# 2_IOConvert.net
KiCad netlist of a schematic drawn in Altium Designer
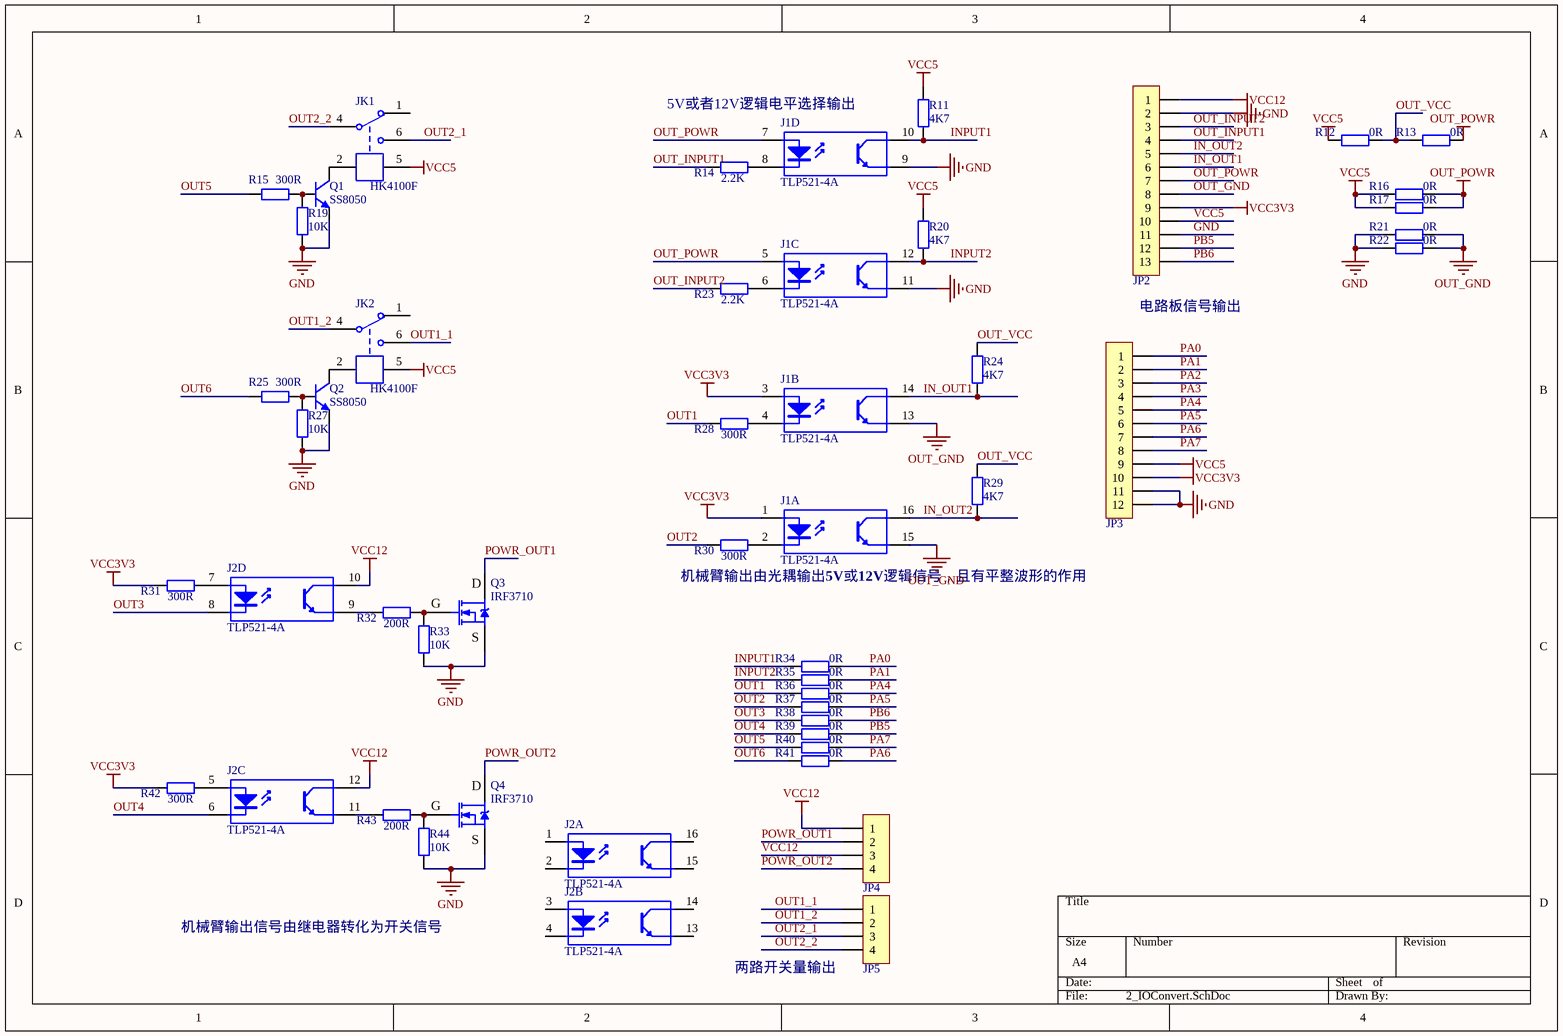
[diagram p0: 2_IOConvert.SchDoc]

(export (version "E")
  (design (tool "Eeschema 10.0.6"))
  (components
    (comp (ref "J1")
      (value "TLP521-4A")
      (footprint "SOP16_M")
      (description "4路开关光耦")
      (fields (field (name "版权归属") "源创客"))
      (libsource (lib "11.1 - 传感元件") (part "TLP521-4A"))
    )
    (comp (ref "J2")
      (value "TLP521-4A")
      (footprint "SOP16_M")
      (description "4路开关光耦")
      (fields (field (name "版权归属") "源创客"))
      (libsource (lib "11.1 - 传感元件") (part "TLP521-4A"))
    )
    (comp (ref "JK1")
      (value "HK4100F")
      (footprint "HK4100F")
      (description "一组转换")
      (fields (field (name "版权归属") "源创客"))
      (libsource (lib "7.1   - 继电器") (part "HK4100F"))
    )
    (comp (ref "JK2")
      (value "HK4100F")
      (footprint "HK4100F")
      (description "一组转换")
      (fields (field (name "版权归属") "源创客"))
      (libsource (lib "7.1   - 继电器") (part "HK4100F"))
    )
    (comp (ref "JP2")
      (value "HDR-1X13")
      (footprint "KF128-3.81-13P")
      (description "13P接插件")
      (fields (field (name "版权归属") "源创客"))
      (libsource (lib "4.7   - 接插件-脚距3.81") (part "Header 13"))
    )
    (comp (ref "JP3")
      (value "HDR-1X12")
      (footprint "KF128-3.81-12P")
      (description "12P接插件")
      (fields (field (name "版权归属") "源创客"))
      (libsource (lib "4.7   - 接插件-脚距3.81") (part "Header 12"))
    )
    (comp (ref "JP4")
      (value "HDR-1X4")
      (footprint "KF128-3.81-4P")
      (description "4P接插件")
      (fields (field (name "版权归属") "源创客"))
      (libsource (lib "4.7   - 接插件-脚距3.81") (part "Header 4"))
    )
    (comp (ref "JP5")
      (value "HDR-1X4")
      (footprint "KF128-3.81-4P")
      (description "4P接插件")
      (fields (field (name "版权归属") "源创客"))
      (libsource (lib "4.7   - 接插件-脚距3.81") (part "Header 4"))
    )
    (comp (ref "Q1")
      (value "SS8050")
      (footprint "SOT23-3L")
      (description "高频放大-NPN型")
      (fields (field (name "版权归属") "源创客"))
      (libsource (lib "6.2   - 三极管") (part "8050-SMD"))
    )
    (comp (ref "Q2")
      (value "SS8050")
      (footprint "SOT23-3L")
      (description "高频放大-NPN型")
      (fields (field (name "版权归属") "源创客"))
      (libsource (lib "6.2   - 三极管") (part "8050-SMD"))
    )
    (comp (ref "Q3")
      (value "IRF3710")
      (footprint "TO252")
      (description "N沟场效应管")
      (fields (field (name "版权归属") "源创客"))
      (libsource (lib "6.1   - 场效应管-可控硅") (part "IRF3710"))
    )
    (comp (ref "Q4")
      (value "IRF3710")
      (footprint "TO252")
      (description "N沟场效应管")
      (fields (field (name "版权归属") "源创客"))
      (libsource (lib "6.1   - 场效应管-可控硅") (part "IRF3710"))
    )
    (comp (ref "R11")
      (value "4K7")
      (footprint "LC-0603_R")
      (description "贴片电阻")
      (libsource (lib "") (part "0603 680KΩ (6803) 1%_2"))
    )
    (comp (ref "R12")
      (value "0R")
      (footprint "LC-0603_R")
      (description "贴片电阻")
      (libsource (lib "") (part "0603 680KΩ (6803) 1%_1"))
    )
    (comp (ref "R13")
      (value "0R")
      (footprint "LC-0603_R")
      (description "贴片电阻")
      (libsource (lib "") (part "0603 680KΩ (6803) 1%_1"))
    )
    (comp (ref "R14")
      (value "2.2K")
      (footprint "LC-0603_R")
      (description "贴片电阻")
      (libsource (lib "Miscellaneous Devices LC") (part "0603 680KΩ (6803) 1%"))
    )
    (comp (ref "R15")
      (value "300R")
      (footprint "LC-0603_R")
      (description "贴片电阻")
      (libsource (lib "") (part "0603 680KΩ (6803) 1%_3"))
    )
    (comp (ref "R16")
      (value "0R")
      (footprint "LC-0603_R")
      (description "贴片电阻")
      (libsource (lib "") (part "0603 680KΩ (6803) 1%_1"))
    )
    (comp (ref "R17")
      (value "0R")
      (footprint "LC-0603_R")
      (description "贴片电阻")
      (libsource (lib "") (part "0603 680KΩ (6803) 1%_1"))
    )
    (comp (ref "R19")
      (value "10K")
      (footprint "LC-0603_R")
      (description "贴片电阻")
      (libsource (lib "") (part "0603 680KΩ (6803) 1%_2"))
    )
    (comp (ref "R20")
      (value "4K7")
      (footprint "LC-0603_R")
      (description "贴片电阻")
      (libsource (lib "") (part "0603 680KΩ (6803) 1%_2"))
    )
    (comp (ref "R21")
      (value "0R")
      (footprint "LC-0603_R")
      (description "贴片电阻")
      (libsource (lib "") (part "0603 680KΩ (6803) 1%_1"))
    )
    (comp (ref "R22")
      (value "0R")
      (footprint "LC-0603_R")
      (description "贴片电阻")
      (libsource (lib "") (part "0603 680KΩ (6803) 1%_1"))
    )
    (comp (ref "R23")
      (value "2.2K")
      (footprint "LC-0603_R")
      (description "贴片电阻")
      (libsource (lib "Miscellaneous Devices LC") (part "0603 680KΩ (6803) 1%"))
    )
    (comp (ref "R24")
      (value "4K7")
      (footprint "LC-0603_R")
      (description "贴片电阻")
      (libsource (lib "") (part "0603 680KΩ (6803) 1%_2"))
    )
    (comp (ref "R25")
      (value "300R")
      (footprint "LC-0603_R")
      (description "贴片电阻")
      (libsource (lib "") (part "0603 680KΩ (6803) 1%_3"))
    )
    (comp (ref "R27")
      (value "10K")
      (footprint "LC-0603_R")
      (description "贴片电阻")
      (libsource (lib "") (part "0603 680KΩ (6803) 1%_2"))
    )
    (comp (ref "R28")
      (value "300R")
      (footprint "LC-0603_R")
      (description "贴片电阻")
      (libsource (lib "Miscellaneous Devices LC") (part "0603 680KΩ (6803) 1%"))
    )
    (comp (ref "R29")
      (value "4K7")
      (footprint "LC-0603_R")
      (description "贴片电阻")
      (libsource (lib "") (part "0603 680KΩ (6803) 1%_2"))
    )
    (comp (ref "R30")
      (value "300R")
      (footprint "LC-0603_R")
      (description "贴片电阻")
      (libsource (lib "Miscellaneous Devices LC") (part "0603 680KΩ (6803) 1%"))
    )
    (comp (ref "R31")
      (value "300R")
      (footprint "LC-0603_R")
      (description "贴片电阻")
      (libsource (lib "Miscellaneous Devices LC") (part "0603 680KΩ (6803) 1%"))
    )
    (comp (ref "R32")
      (value "200R")
      (footprint "LC-0603_R")
      (description "贴片电阻")
      (libsource (lib "Miscellaneous Devices LC") (part "0603 680KΩ (6803) 1%"))
    )
    (comp (ref "R33")
      (value "10K")
      (footprint "LC-0603_R")
      (description "贴片电阻")
      (libsource (lib "") (part "0603 680KΩ (6803) 1%_2"))
    )
    (comp (ref "R34")
      (value "0R")
      (footprint "LC-0603_R")
      (description "贴片电阻")
      (libsource (lib "") (part "0603 680KΩ (6803) 1%_1"))
    )
    (comp (ref "R35")
      (value "0R")
      (footprint "LC-0603_R")
      (description "贴片电阻")
      (libsource (lib "") (part "0603 680KΩ (6803) 1%_1"))
    )
    (comp (ref "R36")
      (value "0R")
      (footprint "LC-0603_R")
      (description "贴片电阻")
      (libsource (lib "") (part "0603 680KΩ (6803) 1%_1"))
    )
    (comp (ref "R37")
      (value "0R")
      (footprint "LC-0603_R")
      (description "贴片电阻")
      (libsource (lib "") (part "0603 680KΩ (6803) 1%_1"))
    )
    (comp (ref "R38")
      (value "0R")
      (footprint "LC-0603_R")
      (description "贴片电阻")
      (libsource (lib "") (part "0603 680KΩ (6803) 1%_1"))
    )
    (comp (ref "R39")
      (value "0R")
      (footprint "LC-0603_R")
      (description "贴片电阻")
      (libsource (lib "") (part "0603 680KΩ (6803) 1%_1"))
    )
    (comp (ref "R40")
      (value "0R")
      (footprint "LC-0603_R")
      (description "贴片电阻")
      (libsource (lib "") (part "0603 680KΩ (6803) 1%_1"))
    )
    (comp (ref "R41")
      (value "0R")
      (footprint "LC-0603_R")
      (description "贴片电阻")
      (libsource (lib "") (part "0603 680KΩ (6803) 1%_1"))
    )
    (comp (ref "R42")
      (value "300R")
      (footprint "LC-0603_R")
      (description "贴片电阻")
      (libsource (lib "Miscellaneous Devices LC") (part "0603 680KΩ (6803) 1%"))
    )
    (comp (ref "R43")
      (value "200R")
      (footprint "LC-0603_R")
      (description "贴片电阻")
      (libsource (lib "Miscellaneous Devices LC") (part "0603 680KΩ (6803) 1%"))
    )
    (comp (ref "R44")
      (value "10K")
      (footprint "LC-0603_R")
      (description "贴片电阻")
      (libsource (lib "") (part "0603 680KΩ (6803) 1%_2"))
    )
  )
  (nets
    (net (code "1") (name "/INPUT1") (class "Default")
      (node (ref "J1") (pin "10") (pinfunction "4C_10") (pintype "passive"))
      (node (ref "R11") (pin "1") (pinfunction "1_1") (pintype "passive"))
      (node (ref "R34") (pin "2") (pinfunction "2_2") (pintype "passive"))
    )
    (net (code "2") (name "/INPUT2") (class "Default")
      (node (ref "J1") (pin "12") (pinfunction "3C_12") (pintype "passive"))
      (node (ref "R20") (pin "1") (pinfunction "1_1") (pintype "passive"))
      (node (ref "R35") (pin "2") (pinfunction "2_2") (pintype "passive"))
    )
    (net (code "3") (name "/IN_OUT1") (class "Default")
      (node (ref "J1") (pin "14") (pinfunction "2C_14") (pintype "passive"))
      (node (ref "JP2") (pin "6") (pinfunction "6_6") (pintype "passive"))
      (node (ref "R24") (pin "1") (pinfunction "1_1") (pintype "passive"))
    )
    (net (code "4") (name "/IN_OUT2") (class "Default")
      (node (ref "J1") (pin "16") (pinfunction "1C_16") (pintype "passive"))
      (node (ref "JP2") (pin "5") (pinfunction "5_5") (pintype "passive"))
      (node (ref "R29") (pin "1") (pinfunction "1_1") (pintype "passive"))
    )
    (net (code "5") (name "/OUT1") (class "Default")
      (node (ref "R28") (pin "2") (pinfunction "2_2") (pintype "passive"))
      (node (ref "R36") (pin "2") (pinfunction "2_2") (pintype "passive"))
    )
    (net (code "6") (name "/OUT1_1") (class "Default")
      (node (ref "JK2") (pin "6") (pinfunction "6_6") (pintype "passive"))
      (node (ref "JP5") (pin "1") (pinfunction "1_1") (pintype "passive"))
    )
    (net (code "7") (name "/OUT1_2") (class "Default")
      (node (ref "JK2") (pin "4") (pinfunction "4_4") (pintype "passive"))
      (node (ref "JP5") (pin "2") (pinfunction "2_2") (pintype "passive"))
    )
    (net (code "8") (name "/OUT2") (class "Default")
      (node (ref "R30") (pin "2") (pinfunction "2_2") (pintype "passive"))
      (node (ref "R37") (pin "2") (pinfunction "2_2") (pintype "passive"))
    )
    (net (code "9") (name "/OUT2_1") (class "Default")
      (node (ref "JK1") (pin "6") (pinfunction "6_6") (pintype "passive"))
      (node (ref "JP5") (pin "3") (pinfunction "3_3") (pintype "passive"))
    )
    (net (code "10") (name "/OUT2_2") (class "Default")
      (node (ref "JK1") (pin "4") (pinfunction "4_4") (pintype "passive"))
      (node (ref "JP5") (pin "4") (pinfunction "4_4") (pintype "passive"))
    )
    (net (code "11") (name "/OUT3") (class "Default")
      (node (ref "J2") (pin "8") (pinfunction "4K_8") (pintype "passive"))
      (node (ref "R38") (pin "2") (pinfunction "2_2") (pintype "passive"))
    )
    (net (code "12") (name "/OUT4") (class "Default")
      (node (ref "J2") (pin "6") (pinfunction "3K_6") (pintype "passive"))
      (node (ref "R39") (pin "2") (pinfunction "2_2") (pintype "passive"))
    )
    (net (code "13") (name "/OUT5") (class "Default")
      (node (ref "R15") (pin "1") (pinfunction "1_1") (pintype "passive"))
      (node (ref "R40") (pin "2") (pinfunction "2_2") (pintype "passive"))
    )
    (net (code "14") (name "/OUT6") (class "Default")
      (node (ref "R25") (pin "1") (pinfunction "1_1") (pintype "passive"))
      (node (ref "R41") (pin "2") (pinfunction "2_2") (pintype "passive"))
    )
    (net (code "15") (name "/OUT_INPUT1") (class "Default")
      (node (ref "JP2") (pin "4") (pinfunction "4_4") (pintype "passive"))
      (node (ref "R14") (pin "2") (pinfunction "2_2") (pintype "passive"))
    )
    (net (code "16") (name "/OUT_INPUT2") (class "Default")
      (node (ref "JP2") (pin "3") (pinfunction "3_3") (pintype "passive"))
      (node (ref "R23") (pin "2") (pinfunction "2_2") (pintype "passive"))
    )
    (net (code "17") (name "/OUT_VCC") (class "Default")
      (node (ref "R12") (pin "1") (pinfunction "1_1") (pintype "passive"))
      (node (ref "R13") (pin "2") (pinfunction "2_2") (pintype "passive"))
      (node (ref "R24") (pin "2") (pinfunction "2_2") (pintype "passive"))
      (node (ref "R29") (pin "2") (pinfunction "2_2") (pintype "passive"))
    )
    (net (code "18") (name "/PA0") (class "Default")
      (node (ref "JP3") (pin "1") (pinfunction "1_1") (pintype "passive"))
      (node (ref "R34") (pin "1") (pinfunction "1_1") (pintype "passive"))
    )
    (net (code "19") (name "/PA1") (class "Default")
      (node (ref "JP3") (pin "2") (pinfunction "2_2") (pintype "passive"))
      (node (ref "R35") (pin "1") (pinfunction "1_1") (pintype "passive"))
    )
    (net (code "20") (name "/PA2") (class "Default")
      (node (ref "JP3") (pin "3") (pinfunction "3_3") (pintype "passive"))
    )
    (net (code "21") (name "/PA3") (class "Default")
      (node (ref "JP3") (pin "4") (pinfunction "4_4") (pintype "passive"))
    )
    (net (code "22") (name "/PA4") (class "Default")
      (node (ref "JP3") (pin "5") (pinfunction "5_5") (pintype "passive"))
      (node (ref "R36") (pin "1") (pinfunction "1_1") (pintype "passive"))
    )
    (net (code "23") (name "/PA5") (class "Default")
      (node (ref "JP3") (pin "6") (pinfunction "6_6") (pintype "passive"))
      (node (ref "R37") (pin "1") (pinfunction "1_1") (pintype "passive"))
    )
    (net (code "24") (name "/PA6") (class "Default")
      (node (ref "JP3") (pin "7") (pinfunction "7_7") (pintype "passive"))
      (node (ref "R41") (pin "1") (pinfunction "1_1") (pintype "passive"))
    )
    (net (code "25") (name "/PA7") (class "Default")
      (node (ref "JP3") (pin "8") (pinfunction "8_8") (pintype "passive"))
      (node (ref "R40") (pin "1") (pinfunction "1_1") (pintype "passive"))
    )
    (net (code "26") (name "/PB5") (class "Default")
      (node (ref "JP2") (pin "12") (pinfunction "12_12") (pintype "passive"))
      (node (ref "R39") (pin "1") (pinfunction "1_1") (pintype "passive"))
    )
    (net (code "27") (name "/PB6") (class "Default")
      (node (ref "JP2") (pin "13") (pinfunction "13_13") (pintype "passive"))
      (node (ref "R38") (pin "1") (pinfunction "1_1") (pintype "passive"))
    )
    (net (code "28") (name "/POWR_OUT1") (class "Default")
      (node (ref "JP4") (pin "2") (pinfunction "2_2") (pintype "passive"))
      (node (ref "Q3") (pin "2") (pinfunction "D_2") (pintype "passive"))
    )
    (net (code "29") (name "/POWR_OUT2") (class "Default")
      (node (ref "JP4") (pin "4") (pinfunction "4_4") (pintype "passive"))
      (node (ref "Q4") (pin "2") (pinfunction "D_2") (pintype "passive"))
    )
    (net (code "30") (name "GND") (class "Default")
      (node (ref "J1") (pin "11") (pinfunction "3E_11") (pintype "passive"))
      (node (ref "J1") (pin "9") (pinfunction "4E_9") (pintype "passive"))
      (node (ref "JP2") (pin "11") (pinfunction "11_11") (pintype "passive"))
      (node (ref "JP2") (pin "2") (pinfunction "2_2") (pintype "passive"))
      (node (ref "JP3") (pin "11") (pinfunction "11_11") (pintype "passive"))
      (node (ref "JP3") (pin "12") (pinfunction "12_12") (pintype "passive"))
      (node (ref "Q1") (pin "2") (pinfunction "E_2") (pintype "passive"))
      (node (ref "Q2") (pin "2") (pinfunction "E_2") (pintype "passive"))
      (node (ref "Q3") (pin "3") (pinfunction "S_3") (pintype "passive"))
      (node (ref "Q4") (pin "3") (pinfunction "S_3") (pintype "passive"))
      (node (ref "R19") (pin "1") (pinfunction "1_1") (pintype "passive"))
      (node (ref "R21") (pin "2") (pinfunction "2_2") (pintype "passive"))
      (node (ref "R22") (pin "2") (pinfunction "2_2") (pintype "passive"))
      (node (ref "R27") (pin "1") (pinfunction "1_1") (pintype "passive"))
      (node (ref "R33") (pin "1") (pinfunction "1_1") (pintype "passive"))
      (node (ref "R44") (pin "1") (pinfunction "1_1") (pintype "passive"))
    )
    (net (code "31") (name "Net-(J1A-1K)") (class "Default")
      (node (ref "J1") (pin "2") (pinfunction "1K_2") (pintype "passive"))
      (node (ref "R30") (pin "1") (pinfunction "1_1") (pintype "passive"))
    )
    (net (code "32") (name "Net-(J1B-2K)") (class "Default")
      (node (ref "J1") (pin "4") (pinfunction "2K_4") (pintype "passive"))
      (node (ref "R28") (pin "1") (pinfunction "1_1") (pintype "passive"))
    )
    (net (code "33") (name "Net-(J1C-3K)") (class "Default")
      (node (ref "J1") (pin "6") (pinfunction "3K_6") (pintype "passive"))
      (node (ref "R23") (pin "1") (pinfunction "1_1") (pintype "passive"))
    )
    (net (code "34") (name "Net-(J1D-4K)") (class "Default")
      (node (ref "J1") (pin "8") (pinfunction "4K_8") (pintype "passive"))
      (node (ref "R14") (pin "1") (pinfunction "1_1") (pintype "passive"))
    )
    (net (code "35") (name "Net-(J2C-3A)") (class "Default")
      (node (ref "J2") (pin "5") (pinfunction "3A_5") (pintype "passive"))
      (node (ref "R42") (pin "1") (pinfunction "1_1") (pintype "passive"))
    )
    (net (code "36") (name "Net-(J2C-3E)") (class "Default")
      (node (ref "J2") (pin "11") (pinfunction "3E_11") (pintype "passive"))
      (node (ref "R43") (pin "2") (pinfunction "2_2") (pintype "passive"))
    )
    (net (code "37") (name "Net-(J2D-4A)") (class "Default")
      (node (ref "J2") (pin "7") (pinfunction "4A_7") (pintype "passive"))
      (node (ref "R31") (pin "1") (pinfunction "1_1") (pintype "passive"))
    )
    (net (code "38") (name "Net-(J2D-4E)") (class "Default")
      (node (ref "J2") (pin "9") (pinfunction "4E_9") (pintype "passive"))
      (node (ref "R32") (pin "2") (pinfunction "2_2") (pintype "passive"))
    )
    (net (code "39") (name "Net-(Q1-B)") (class "Default")
      (node (ref "Q1") (pin "1") (pinfunction "B_1") (pintype "passive"))
      (node (ref "R15") (pin "2") (pinfunction "2_2") (pintype "passive"))
      (node (ref "R19") (pin "2") (pinfunction "2_2") (pintype "passive"))
    )
    (net (code "40") (name "Net-(Q1-C)") (class "Default")
      (node (ref "JK1") (pin "2") (pinfunction "2_2") (pintype "passive"))
      (node (ref "Q1") (pin "3") (pinfunction "C_3") (pintype "passive"))
    )
    (net (code "41") (name "Net-(Q2-B)") (class "Default")
      (node (ref "Q2") (pin "1") (pinfunction "B_1") (pintype "passive"))
      (node (ref "R25") (pin "2") (pinfunction "2_2") (pintype "passive"))
      (node (ref "R27") (pin "2") (pinfunction "2_2") (pintype "passive"))
    )
    (net (code "42") (name "Net-(Q2-C)") (class "Default")
      (node (ref "JK2") (pin "2") (pinfunction "2_2") (pintype "passive"))
      (node (ref "Q2") (pin "3") (pinfunction "C_3") (pintype "passive"))
    )
    (net (code "43") (name "Net-(Q3-G)") (class "Default")
      (node (ref "Q3") (pin "1") (pinfunction "G_1") (pintype "passive"))
      (node (ref "R32") (pin "1") (pinfunction "1_1") (pintype "passive"))
      (node (ref "R33") (pin "2") (pinfunction "2_2") (pintype "passive"))
    )
    (net (code "44") (name "Net-(Q4-G)") (class "Default")
      (node (ref "Q4") (pin "1") (pinfunction "G_1") (pintype "passive"))
      (node (ref "R43") (pin "1") (pinfunction "1_1") (pintype "passive"))
      (node (ref "R44") (pin "2") (pinfunction "2_2") (pintype "passive"))
    )
    (net (code "45") (name "OUT_GND") (class "Default")
      (node (ref "J1") (pin "13") (pinfunction "2E_13") (pintype "passive"))
      (node (ref "J1") (pin "15") (pinfunction "1E_15") (pintype "passive"))
      (node (ref "JP2") (pin "8") (pinfunction "8_8") (pintype "passive"))
      (node (ref "R21") (pin "1") (pinfunction "1_1") (pintype "passive"))
      (node (ref "R22") (pin "1") (pinfunction "1_1") (pintype "passive"))
    )
    (net (code "46") (name "OUT_POWR") (class "Default")
      (node (ref "J1") (pin "5") (pinfunction "3A_5") (pintype "passive"))
      (node (ref "J1") (pin "7") (pinfunction "4A_7") (pintype "passive"))
      (node (ref "JP2") (pin "7") (pinfunction "7_7") (pintype "passive"))
      (node (ref "R13") (pin "1") (pinfunction "1_1") (pintype "passive"))
      (node (ref "R16") (pin "1") (pinfunction "1_1") (pintype "passive"))
      (node (ref "R17") (pin "1") (pinfunction "1_1") (pintype "passive"))
    )
    (net (code "47") (name "VCC3V3") (class "Default")
      (node (ref "J1") (pin "1") (pinfunction "1A_1") (pintype "passive"))
      (node (ref "J1") (pin "3") (pinfunction "2A_3") (pintype "passive"))
      (node (ref "JP2") (pin "9") (pinfunction "9_9") (pintype "passive"))
      (node (ref "JP3") (pin "10") (pinfunction "10_10") (pintype "passive"))
      (node (ref "R31") (pin "2") (pinfunction "2_2") (pintype "passive"))
      (node (ref "R42") (pin "2") (pinfunction "2_2") (pintype "passive"))
    )
    (net (code "48") (name "VCC5") (class "Default")
      (node (ref "JK1") (pin "5") (pinfunction "5_5") (pintype "passive"))
      (node (ref "JK2") (pin "5") (pinfunction "5_5") (pintype "passive"))
      (node (ref "JP2") (pin "10") (pinfunction "10_10") (pintype "passive"))
      (node (ref "JP3") (pin "9") (pinfunction "9_9") (pintype "passive"))
      (node (ref "R11") (pin "2") (pinfunction "2_2") (pintype "passive"))
      (node (ref "R12") (pin "2") (pinfunction "2_2") (pintype "passive"))
      (node (ref "R16") (pin "2") (pinfunction "2_2") (pintype "passive"))
      (node (ref "R17") (pin "2") (pinfunction "2_2") (pintype "passive"))
      (node (ref "R20") (pin "2") (pinfunction "2_2") (pintype "passive"))
    )
    (net (code "49") (name "VCC12") (class "Default")
      (node (ref "J2") (pin "10") (pinfunction "4C_10") (pintype "passive"))
      (node (ref "J2") (pin "12") (pinfunction "3C_12") (pintype "passive"))
      (node (ref "JP2") (pin "1") (pinfunction "1_1") (pintype "passive"))
      (node (ref "JP4") (pin "1") (pinfunction "1_1") (pintype "passive"))
      (node (ref "JP4") (pin "3") (pinfunction "3_3") (pintype "passive"))
    )
    (net (code "50") (name "unconnected-(J2A-1A-Pad1)") (class "Default")
      (node (ref "J2") (pin "1") (pinfunction "1A_1") (pintype "passive"))
    )
    (net (code "51") (name "unconnected-(J2A-1C-Pad16)") (class "Default")
      (node (ref "J2") (pin "16") (pinfunction "1C_16") (pintype "passive"))
    )
    (net (code "52") (name "unconnected-(J2A-1E-Pad15)") (class "Default")
      (node (ref "J2") (pin "15") (pinfunction "1E_15") (pintype "passive"))
    )
    (net (code "53") (name "unconnected-(J2A-1K-Pad2)") (class "Default")
      (node (ref "J2") (pin "2") (pinfunction "1K_2") (pintype "passive"))
    )
    (net (code "54") (name "unconnected-(J2B-2A-Pad3)") (class "Default")
      (node (ref "J2") (pin "3") (pinfunction "2A_3") (pintype "passive"))
    )
    (net (code "55") (name "unconnected-(J2B-2C-Pad14)") (class "Default")
      (node (ref "J2") (pin "14") (pinfunction "2C_14") (pintype "passive"))
    )
    (net (code "56") (name "unconnected-(J2B-2E-Pad13)") (class "Default")
      (node (ref "J2") (pin "13") (pinfunction "2E_13") (pintype "passive"))
    )
    (net (code "57") (name "unconnected-(J2B-2K-Pad4)") (class "Default")
      (node (ref "J2") (pin "4") (pinfunction "2K_4") (pintype "passive"))
    )
    (net (code "58") (name "unconnected-(JK1-Pad1)") (class "Default")
      (node (ref "JK1") (pin "1") (pinfunction "1_1") (pintype "passive"))
    )
    (net (code "59") (name "unconnected-(JK2-Pad1)") (class "Default")
      (node (ref "JK2") (pin "1") (pinfunction "1_1") (pintype "passive"))
    )
  )
)
